# 00B-003.net
KiCad netlist of a schematic drawn in EAGLE
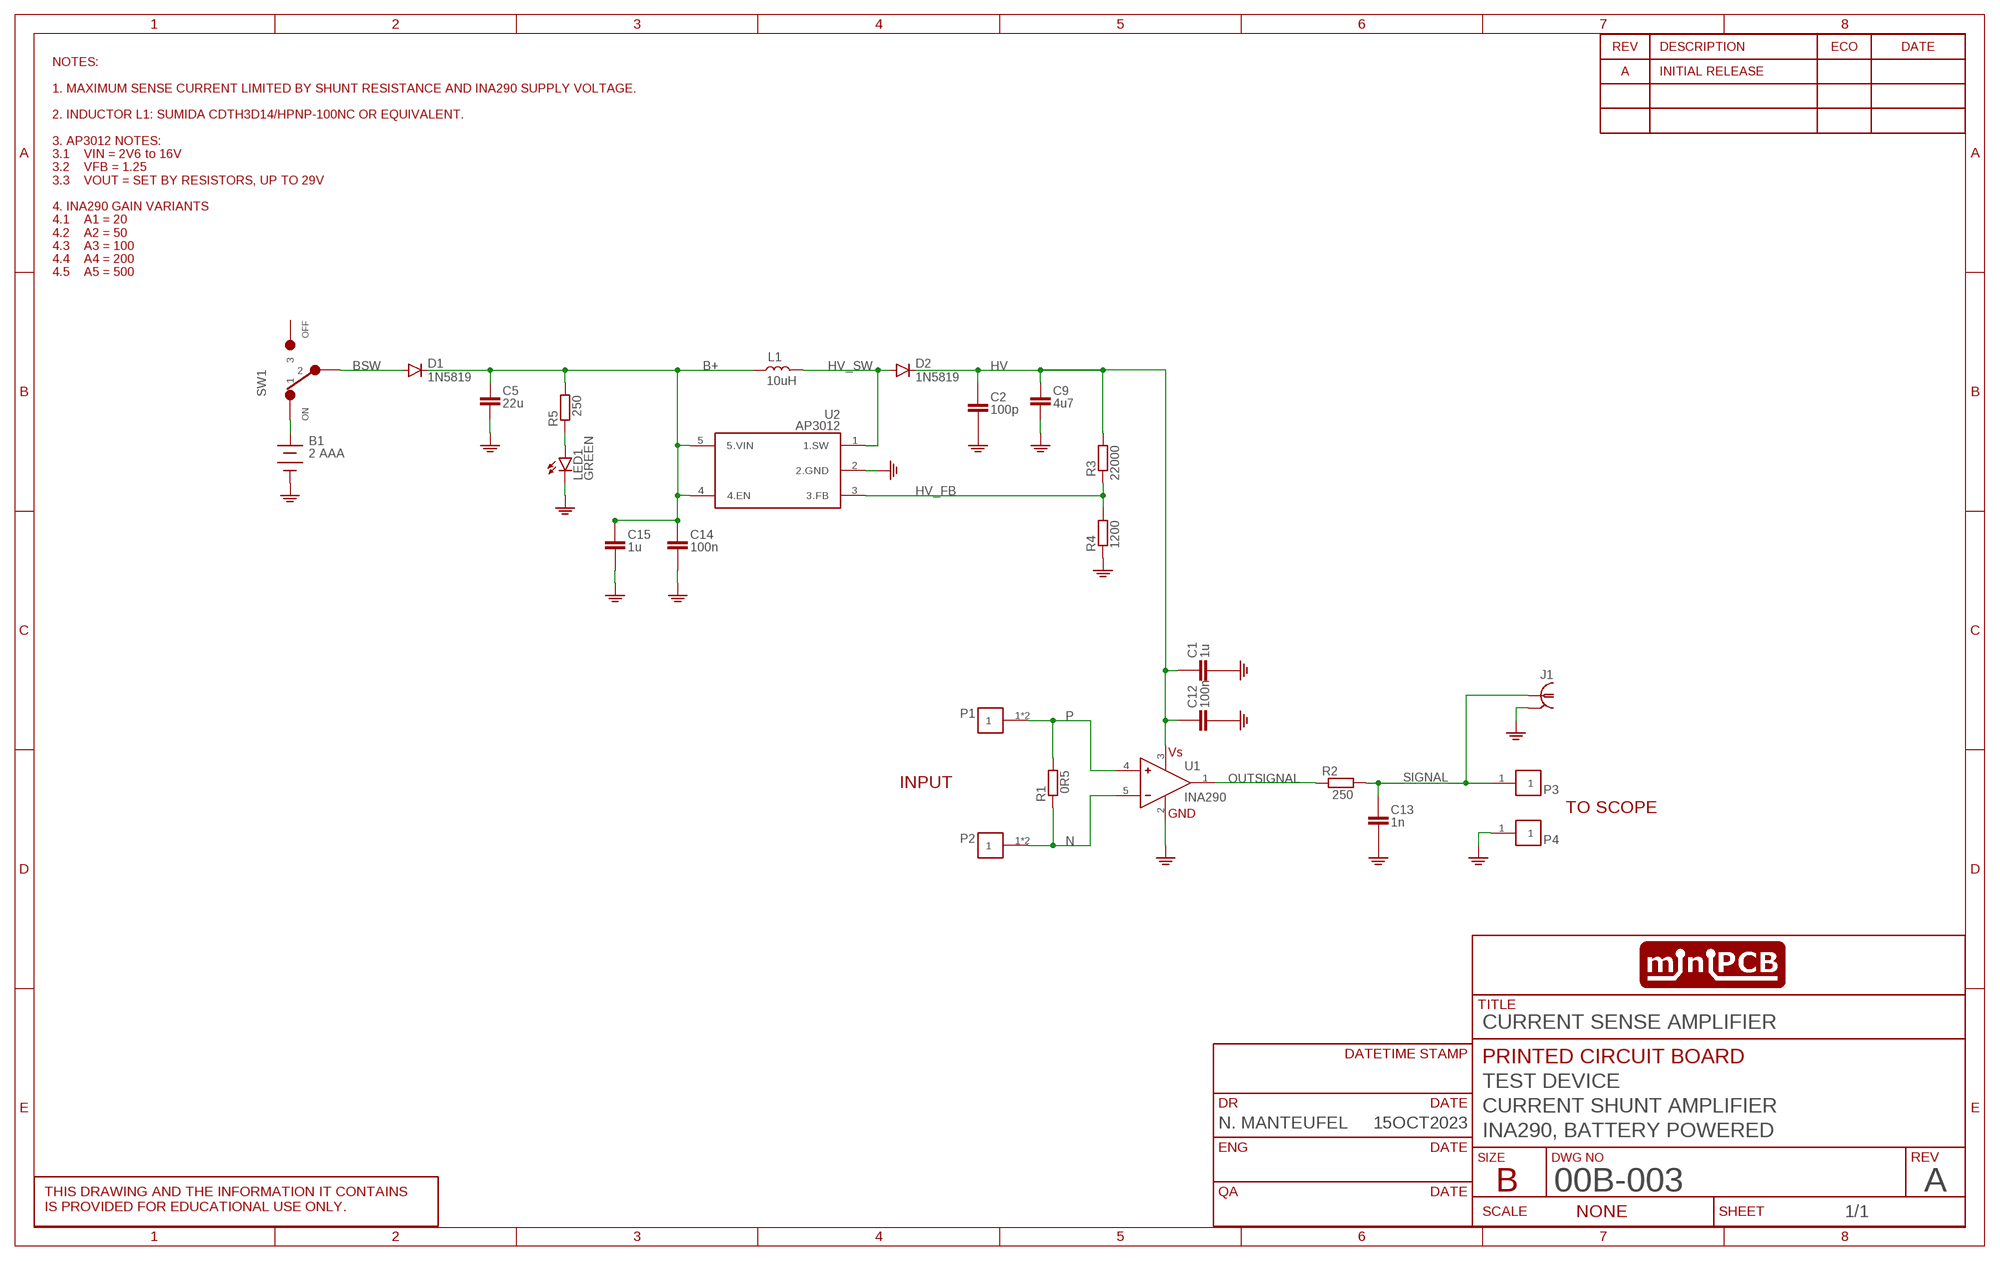
[diagram p0: schematic, sheet 1]

(export (version "E")
  (design (tool "Eeschema 10.0.6"))
  (components
    (comp (ref "B1")
      (value "2 AAA")
      (footprint "eagle-import:2XAAA")
      (libsource (lib "eagle-import") (part "BATTERYAAA"))
    )
    (comp (ref "C1")
      (value "1u")
      (footprint "eagle-import:C0805")
      (libsource (lib "eagle-import") (part "CAPACITORSMD"))
    )
    (comp (ref "C2")
      (value "100p")
      (footprint "eagle-import:C0805")
      (libsource (lib "eagle-import") (part "CAPACITORSMD"))
    )
    (comp (ref "C5")
      (value "22u")
      (footprint "eagle-import:C-PCR-8X10")
      (libsource (lib "eagle-import") (part "C-EUPCR-8X10"))
    )
    (comp (ref "C9")
      (value "4u7")
      (footprint "eagle-import:C-PCR-8X10")
      (libsource (lib "eagle-import") (part "C-EUPCR-8X10"))
    )
    (comp (ref "C12")
      (value "100n")
      (footprint "eagle-import:C0805")
      (libsource (lib "eagle-import") (part "CAPACITORSMD"))
    )
    (comp (ref "C13")
      (value "1n")
      (footprint "eagle-import:C0805")
      (libsource (lib "eagle-import") (part "CAPACITORSMD"))
    )
    (comp (ref "C14")
      (value "100n")
      (footprint "eagle-import:C0805")
      (libsource (lib "eagle-import") (part "CAPACITORSMD"))
    )
    (comp (ref "C15")
      (value "1u")
      (footprint "eagle-import:C0805")
      (libsource (lib "eagle-import") (part "CAPACITORSMD"))
    )
    (comp (ref "D1")
      (value "1N5819")
      (footprint "eagle-import:DO214AC")
      (libsource (lib "eagle-import") (part "DIODESMD"))
    )
    (comp (ref "D2")
      (value "1N5819")
      (footprint "eagle-import:DO214AC")
      (libsource (lib "eagle-import") (part "DIODESMD"))
    )
    (comp (ref "J1")
      (value "BNC_RA")
      (footprint "eagle-import:BNC_RIGHTANGLE")
      (libsource (lib "eagle-import") (part "BNC_RA"))
    )
    (comp (ref "L1")
      (value "10uH")
      (footprint "eagle-import:SRN5040")
      (libsource (lib "eagle-import") (part "L5040"))
    )
    (comp (ref "LED1")
      (value "GREEN")
      (footprint "eagle-import:CHIP-LED0805")
      (libsource (lib "eagle-import") (part "LEDCHIP-LED0805"))
    )
    (comp (ref "P1")
      (value "PINS_124AWG")
      (footprint "eagle-import:PINS_1_1MM")
      (libsource (lib "eagle-import") (part "PINS_124AWG"))
    )
    (comp (ref "P2")
      (value "PINS_124AWG")
      (footprint "eagle-import:PINS_1_1MM")
      (libsource (lib "eagle-import") (part "PINS_124AWG"))
    )
    (comp (ref "P3")
      (value "PINS_1KE_5000")
      (footprint "eagle-import:PINS_1_TESTPOINT_KE5000")
      (libsource (lib "eagle-import") (part "PINS_1KE_5000"))
    )
    (comp (ref "P4")
      (value "PINS_1KE_5000")
      (footprint "eagle-import:PINS_1_TESTPOINT_KE5000")
      (libsource (lib "eagle-import") (part "PINS_1KE_5000"))
    )
    (comp (ref "R1")
      (value "0R5")
      (footprint "eagle-import:R2512K")
      (libsource (lib "eagle-import") (part "RESISTOR2512"))
    )
    (comp (ref "R2")
      (value "250")
      (footprint "eagle-import:R0805")
      (libsource (lib "eagle-import") (part "RESISTORSMD"))
    )
    (comp (ref "R3")
      (value "22000")
      (footprint "eagle-import:R0805")
      (libsource (lib "eagle-import") (part "RESISTORSMD"))
    )
    (comp (ref "R4")
      (value "1200")
      (footprint "eagle-import:R0805")
      (libsource (lib "eagle-import") (part "RESISTORSMD"))
    )
    (comp (ref "R5")
      (value "250")
      (footprint "eagle-import:R0805")
      (libsource (lib "eagle-import") (part "RESISTORSMD"))
    )
    (comp (ref "SW1")
      (value "SWITCH-SPDTCK1001+TEXT")
      (footprint "eagle-import:SWITCH-C&K1001-TEXT")
      (libsource (lib "eagle-import") (part "SWITCH-SPDTCK1001+TEXT"))
    )
    (comp (ref "U1")
      (value "INA290")
      (footprint "eagle-import:SC70-5")
      (libsource (lib "eagle-import") (part "INA290"))
    )
    (comp (ref "U2")
      (value "AP3012")
      (footprint "eagle-import:SOT23-5-K")
      (libsource (lib "eagle-import") (part "AP3012"))
    )
  )
  (nets
    (net (code "1") (name "/B+") (class "Default")
      (node (ref "C14") (pin "1ASD") (pinfunction "+_1ASD") (pintype "passive"))
      (node (ref "C15") (pin "1ASD") (pinfunction "+_1ASD") (pintype "passive"))
      (node (ref "C5") (pin "+") (pinfunction "1_+") (pintype "passive"))
      (node (ref "D1") (pin "C") (pinfunction "C_C") (pintype "passive"))
      (node (ref "L1") (pin "1") (pinfunction "P$1_1") (pintype "passive"))
      (node (ref "R5") (pin "2") (pinfunction "2_2") (pintype "passive"))
      (node (ref "U2") (pin "4") (pinfunction "4.EN_4") (pintype "bidirectional"))
      (node (ref "U2") (pin "5") (pinfunction "5.VIN_5") (pintype "bidirectional"))
    )
    (net (code "2") (name "/BSW") (class "Default")
      (node (ref "D1") (pin "A") (pinfunction "A_A") (pintype "passive"))
      (node (ref "SW1") (pin "2") (pinfunction "2_2") (pintype "bidirectional"))
    )
    (net (code "3") (name "/HV") (class "Default")
      (node (ref "C1") (pin "1ASD") (pinfunction "+_1ASD") (pintype "passive"))
      (node (ref "C12") (pin "1ASD") (pinfunction "+_1ASD") (pintype "passive"))
      (node (ref "C2") (pin "1ASD") (pinfunction "+_1ASD") (pintype "passive"))
      (node (ref "C9") (pin "+") (pinfunction "1_+") (pintype "passive"))
      (node (ref "D2") (pin "C") (pinfunction "C_C") (pintype "passive"))
      (node (ref "R3") (pin "2") (pinfunction "2_2") (pintype "passive"))
      (node (ref "U1") (pin "3") (pinfunction "3.VS_3") (pintype "bidirectional"))
    )
    (net (code "4") (name "/HV_FB") (class "Default")
      (node (ref "R3") (pin "1") (pinfunction "1_1") (pintype "passive"))
      (node (ref "R4") (pin "2") (pinfunction "2_2") (pintype "passive"))
      (node (ref "U2") (pin "3") (pinfunction "3.FB_3") (pintype "bidirectional"))
    )
    (net (code "5") (name "/HV_SW") (class "Default")
      (node (ref "D2") (pin "A") (pinfunction "A_A") (pintype "passive"))
      (node (ref "L1") (pin "2") (pinfunction "P$2_2") (pintype "passive"))
      (node (ref "U2") (pin "1") (pinfunction "1.SW_1") (pintype "bidirectional"))
    )
    (net (code "6") (name "/N") (class "Default")
      (node (ref "P2") (pin "1") (pinfunction "1_1") (pintype "bidirectional"))
      (node (ref "P2") (pin "2") (pinfunction "1_2") (pintype "bidirectional"))
      (node (ref "R1") (pin "1") (pinfunction "1_1") (pintype "passive"))
      (node (ref "U1") (pin "5") (pinfunction "5.-IN_5") (pintype "bidirectional"))
    )
    (net (code "7") (name "/OUTSIGNAL") (class "Default")
      (node (ref "R2") (pin "1") (pinfunction "1_1") (pintype "passive"))
      (node (ref "U1") (pin "1") (pinfunction "1.OUT_1") (pintype "bidirectional"))
    )
    (net (code "8") (name "/P") (class "Default")
      (node (ref "P1") (pin "1") (pinfunction "1_1") (pintype "bidirectional"))
      (node (ref "P1") (pin "2") (pinfunction "1_2") (pintype "bidirectional"))
      (node (ref "R1") (pin "2") (pinfunction "2_2") (pintype "passive"))
      (node (ref "U1") (pin "4") (pinfunction "4.+IN_4") (pintype "bidirectional"))
    )
    (net (code "9") (name "/SIGNAL") (class "Default")
      (node (ref "C13") (pin "1ASD") (pinfunction "+_1ASD") (pintype "passive"))
      (node (ref "J1") (pin "1") (pinfunction "1_1") (pintype "passive"))
      (node (ref "P3") (pin "1") (pinfunction "1_1") (pintype "bidirectional"))
      (node (ref "R2") (pin "2") (pinfunction "2_2") (pintype "passive"))
    )
    (net (code "10") (name "GND") (class "Default")
      (node (ref "B1") (pin "-") (pinfunction "-_-") (pintype "bidirectional"))
      (node (ref "C1") (pin "2ASDF") (pinfunction "-_2ASDF") (pintype "passive"))
      (node (ref "C12") (pin "2ASDF") (pinfunction "-_2ASDF") (pintype "passive"))
      (node (ref "C13") (pin "2ASDF") (pinfunction "-_2ASDF") (pintype "passive"))
      (node (ref "C14") (pin "2ASDF") (pinfunction "-_2ASDF") (pintype "passive"))
      (node (ref "C15") (pin "2ASDF") (pinfunction "-_2ASDF") (pintype "passive"))
      (node (ref "C2") (pin "2ASDF") (pinfunction "-_2ASDF") (pintype "passive"))
      (node (ref "C5") (pin "-") (pinfunction "2_-") (pintype "passive"))
      (node (ref "C9") (pin "-") (pinfunction "2_-") (pintype "passive"))
      (node (ref "J1") (pin "2") (pinfunction "GND_2") (pintype "power_in"))
      (node (ref "LED1") (pin "C") (pinfunction "C_C") (pintype "passive"))
      (node (ref "P4") (pin "1") (pinfunction "1_1") (pintype "bidirectional"))
      (node (ref "R4") (pin "1") (pinfunction "1_1") (pintype "passive"))
      (node (ref "U1") (pin "2") (pinfunction "2.GND_2") (pintype "bidirectional"))
      (node (ref "U2") (pin "2") (pinfunction "2.GND_2") (pintype "bidirectional"))
    )
    (net (code "11") (name "Net-(B1-Pad+)") (class "Default")
      (node (ref "B1") (pin "+") (pinfunction "+_+") (pintype "bidirectional"))
      (node (ref "SW1") (pin "1") (pinfunction "1_1") (pintype "bidirectional"))
    )
    (net (code "12") (name "Net-(LED1-PadA)") (class "Default")
      (node (ref "LED1") (pin "A") (pinfunction "A_A") (pintype "passive"))
      (node (ref "R5") (pin "1") (pinfunction "1_1") (pintype "passive"))
    )
    (net (code "13") (name "unconnected-(SW1-Pad3)") (class "Default")
      (node (ref "SW1") (pin "3") (pinfunction "3_3") (pintype "bidirectional"))
    )
  )
)
